# Battery_Management.net
KiCad netlist of a schematic drawn in Altium Designer
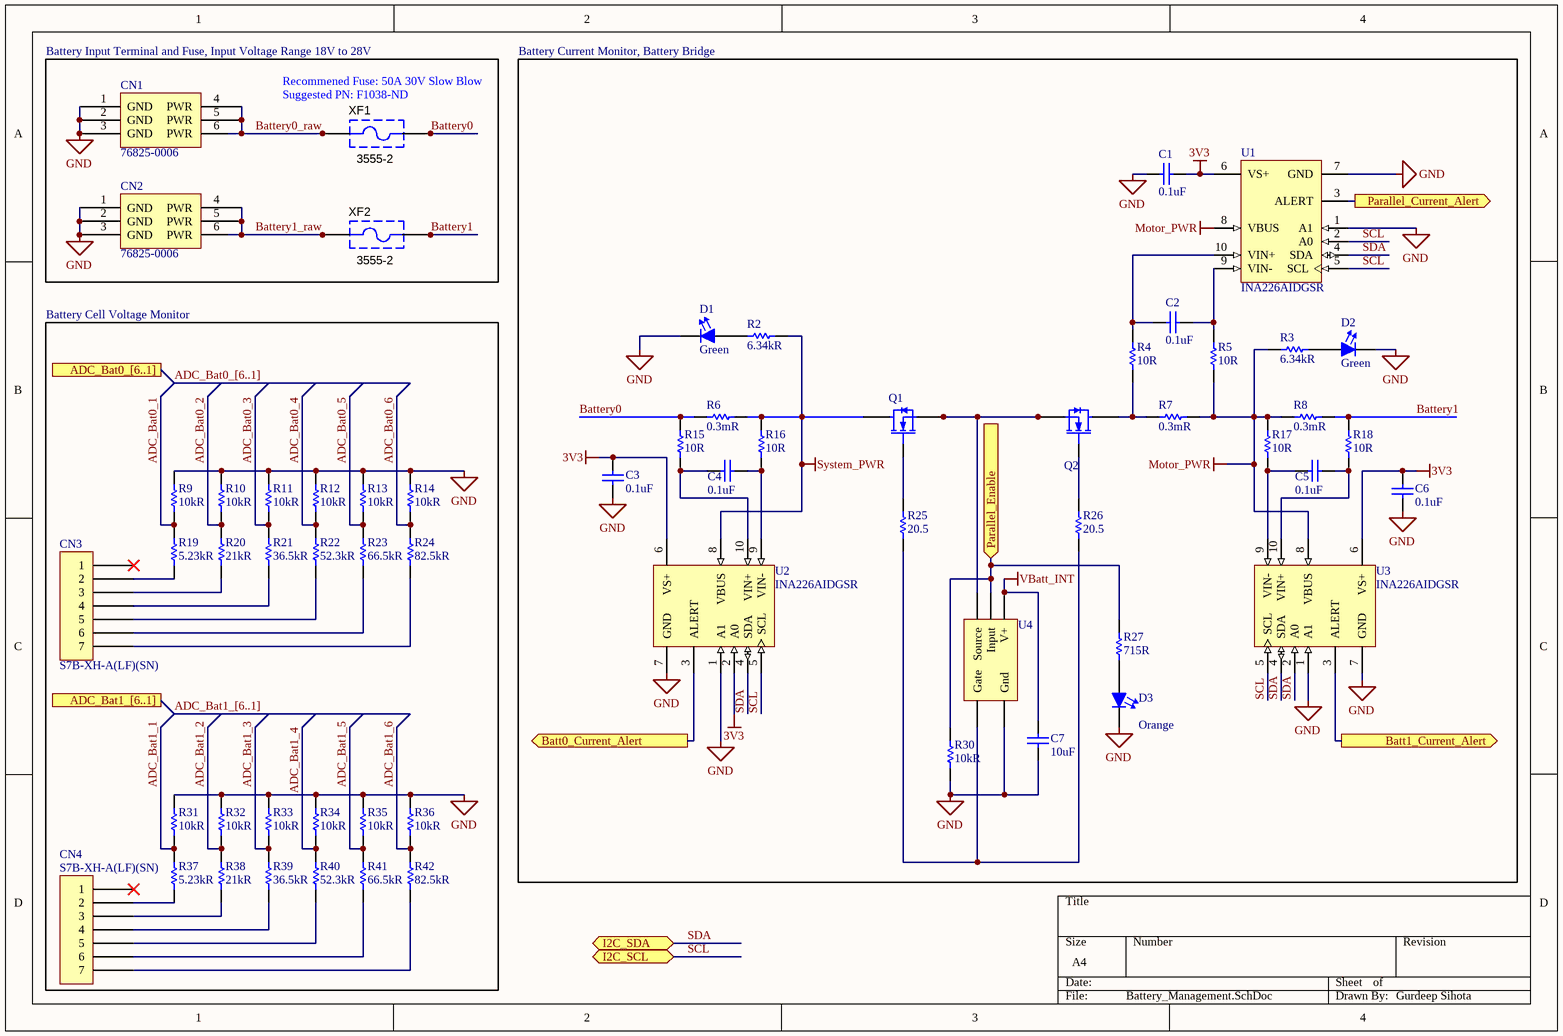
[diagram p0: Battery_Management.SchDoc]

(export (version "E")
  (design (tool "Eeschema 10.0.6"))
  (components
    (comp (ref "C1")
      (value "CL10B104JB8NNNC")
      (footprint "FP-CL10-0_1-IPC_A")
      (description "CAP CER 0.1UF 50V X7R 0603")
      (fields
        (field (name "TOLERANCE") "5%")
        (field (name "VOLTAGE") "50V")
        (field (name "CAPACITANCE") "0.1uF")
      )
      (libsource (lib "AUVIC") (part "CAP-NP-2"))
    )
    (comp (ref "C2")
      (value "CL10B104JB8NNNC")
      (footprint "FP-CL10-0_1-IPC_A")
      (description "CAP CER 0.1UF 50V X7R 0603")
      (fields
        (field (name "TOLERANCE") "5%")
        (field (name "VOLTAGE") "50V")
        (field (name "CAPACITANCE") "0.1uF")
      )
      (libsource (lib "AUVIC") (part "CAP-NP-2"))
    )
    (comp (ref "C3")
      (value "CL10B104JB8NNNC")
      (footprint "FP-CL10-0_1-IPC_A")
      (description "CAP CER 0.1UF 50V X7R 0603")
      (fields
        (field (name "TOLERANCE") "5%")
        (field (name "VOLTAGE") "50V")
        (field (name "CAPACITANCE") "0.1uF")
      )
      (libsource (lib "AUVIC") (part "CAP-NP-2"))
    )
    (comp (ref "C4")
      (value "CL10B104JB8NNNC")
      (footprint "FP-CL10-0_1-IPC_A")
      (description "CAP CER 0.1UF 50V X7R 0603")
      (fields
        (field (name "TOLERANCE") "5%")
        (field (name "VOLTAGE") "50V")
        (field (name "CAPACITANCE") "0.1uF")
      )
      (libsource (lib "AUVIC") (part "CAP-NP-2"))
    )
    (comp (ref "C5")
      (value "CL10B104JB8NNNC")
      (footprint "FP-CL10-0_1-IPC_A")
      (description "CAP CER 0.1UF 50V X7R 0603")
      (fields
        (field (name "TOLERANCE") "5%")
        (field (name "VOLTAGE") "50V")
        (field (name "CAPACITANCE") "0.1uF")
      )
      (libsource (lib "AUVIC") (part "CAP-NP-2"))
    )
    (comp (ref "C6")
      (value "CL10B104JB8NNNC")
      (footprint "FP-CL10-0_1-IPC_A")
      (description "CAP CER 0.1UF 50V X7R 0603")
      (fields
        (field (name "TOLERANCE") "5%")
        (field (name "VOLTAGE") "50V")
        (field (name "CAPACITANCE") "0.1uF")
      )
      (libsource (lib "AUVIC") (part "CAP-NP-2"))
    )
    (comp (ref "C7")
      (value "CL31B106KBHNNNE")
      (footprint "CAPC3216X180X50ML20T30")
      (description "Cap Ceramic 10uF 50V X7R 10% Pad SMD 1206 125°C T/R")
      (fields (field (name "CAPACITANCE") "10uF") (field (name "TOLERANCE") "10%"))
      (libsource (lib "AUVIC") (part "CAP-NP-2"))
    )
    (comp (ref "CN1")
      (value "76825-0006")
      (footprint "76825-0006-Footprint-1")
      (libsource (lib "AUVIC") (part "76825-0006"))
    )
    (comp (ref "CN2")
      (value "76825-0006")
      (footprint "76825-0006-Footprint-1")
      (libsource (lib "AUVIC") (part "76825-0006"))
    )
    (comp (ref "CN3")
      (value "S7B-XH-A(LF)(SN)")
      (footprint "S7B-XH-A(LF)(SN)-Footprint-1")
      (description "CONN HEADER XH SIDE 7POS 2.5MM")
      (libsource (lib "AUVIC") (part "S7B-XH-A(LF)(SN)"))
    )
    (comp (ref "CN4")
      (value "S7B-XH-A(LF)(SN)")
      (footprint "S7B-XH-A(LF)(SN)-Footprint-1")
      (description "CONN HEADER XH SIDE 7POS 2.5MM")
      (libsource (lib "AUVIC") (part "S7B-XH-A(LF)(SN)"))
    )
    (comp (ref "D1")
      (value "LT Q39G-Q1OO-25-1")
      (footprint "FP-LB_Q39E-MFG")
      (description "LED GREEN DIFFUSED 0603 SMD")
      (fields (field (name "COLOR") "Green"))
      (libsource (lib "") (part "Symbol_1"))
    )
    (comp (ref "D2")
      (value "LT Q39G-Q1OO-25-1")
      (footprint "FP-LB_Q39E-MFG")
      (description "LED GREEN DIFFUSED 0603 SMD")
      (fields (field (name "COLOR") "Green"))
      (libsource (lib "") (part "Symbol_1"))
    )
    (comp (ref "D3")
      (value "LED, 0805 (2012), Orange, Clear")
      (footprint "LED0805")
      (fields (field (name "COLOUR") "Orange") (field (name "CREATED BY") "Robert Keen"))
      (libsource (lib "") (part "Symbol_1"))
    )
    (comp (ref "Q1")
      (value "MOSFET N-Channel, 40V, 100A, 272W")
      (footprint "LFPAK-PowerSO8")
      (description "MOSFET N-Channel, 40V, 100A, 272W, Enh-Mode")
      (fields
        (field (name "MFG") "NXP Semiconductors")
        (field (name "PUBLISHER") "AUVic")
        (field (name "CREATED BY") "Ashwin Sira")
        (field (name "REVIEWED_BY") "Ashwin Sira")
      )
      (libsource (lib "AUVIC") (part "MOSFET N-Channel, 40V, 100A, 272W"))
    )
    (comp (ref "Q2")
      (value "MOSFET N-Channel, 40V, 100A, 272W")
      (footprint "LFPAK-PowerSO8")
      (description "MOSFET N-Channel, 40V, 100A, 272W, Enh-Mode")
      (fields
        (field (name "MFG") "NXP Semiconductors")
        (field (name "PUBLISHER") "AUVic")
        (field (name "CREATED BY") "Ashwin Sira")
        (field (name "REVIEWED_BY") "Ashwin Sira")
      )
      (libsource (lib "AUVIC") (part "MOSFET N-Channel, 40V, 100A, 272W"))
    )
    (comp (ref "R2")
      (value "CRCW06036K34FKEA")
      (footprint "RESC1609X50X30ML10T20")
      (fields (field (name "RESISTANCE") "6.34kR") (field (name "TOLERANCE") "1%"))
      (libsource (lib "AUVIC") (part "RES"))
    )
    (comp (ref "R3")
      (value "CRCW06036K34FKEA")
      (footprint "RESC1609X50X30ML10T20")
      (fields (field (name "RESISTANCE") "6.34kR") (field (name "TOLERANCE") "1%"))
      (libsource (lib "AUVIC") (part "RES"))
    )
    (comp (ref "R4")
      (value "ERJ3EKF10R0V")
      (footprint "FP-ERJ3EK-IPC_A")
      (fields (field (name "RESISTANCE") "10R") (field (name "TOLERANCE") "1%"))
      (libsource (lib "AUVIC") (part "RES"))
    )
    (comp (ref "R5")
      (value "ERJ3EKF10R0V")
      (footprint "FP-ERJ3EK-IPC_A")
      (fields (field (name "RESISTANCE") "10R") (field (name "TOLERANCE") "1%"))
      (libsource (lib "AUVIC") (part "RES"))
    )
    (comp (ref "R6")
      (value "HCS2512FTL300")
      (footprint "RESC6332N(2512\")")
      (fields (field (name "RESISTANCE") "0.3mR") (field (name "TOLERANCE") "1%"))
      (libsource (lib "AUVIC") (part "Symbol"))
    )
    (comp (ref "R7")
      (value "HCS2512FTL300")
      (footprint "RESC6332N(2512\")")
      (fields (field (name "RESISTANCE") "0.3mR") (field (name "TOLERANCE") "1%"))
      (libsource (lib "AUVIC") (part "Symbol"))
    )
    (comp (ref "R8")
      (value "HCS2512FTL300")
      (footprint "RESC6332N(2512\")")
      (fields (field (name "RESISTANCE") "0.3mR") (field (name "TOLERANCE") "1%"))
      (libsource (lib "AUVIC") (part "Symbol"))
    )
    (comp (ref "R9")
      (value "RC0603FR-0710KL")
      (footprint "RESC1608X55X25ML10T15")
      (description "Res General Purpose Thick Film 0603 10K Ohm 1% 1/10W ±100ppm/°C Molded SMD Paper T/R")
      (fields (field (name "RESISTANCE") "10kR") (field (name "TOLERANCE") "1%"))
      (libsource (lib "AUVIC") (part "RES-2"))
    )
    (comp (ref "R10")
      (value "RC0603FR-0710KL")
      (footprint "RESC1608X55X25ML10T15")
      (description "Res General Purpose Thick Film 0603 10K Ohm 1% 1/10W ±100ppm/°C Molded SMD Paper T/R")
      (fields (field (name "RESISTANCE") "10kR") (field (name "TOLERANCE") "1%"))
      (libsource (lib "AUVIC") (part "RES-2"))
    )
    (comp (ref "R11")
      (value "RC0603FR-0710KL")
      (footprint "RESC1608X55X25ML10T15")
      (description "Res General Purpose Thick Film 0603 10K Ohm 1% 1/10W ±100ppm/°C Molded SMD Paper T/R")
      (fields (field (name "RESISTANCE") "10kR") (field (name "TOLERANCE") "1%"))
      (libsource (lib "AUVIC") (part "RES-2"))
    )
    (comp (ref "R12")
      (value "RC0603FR-0710KL")
      (footprint "RESC1608X55X25ML10T15")
      (description "Res General Purpose Thick Film 0603 10K Ohm 1% 1/10W ±100ppm/°C Molded SMD Paper T/R")
      (fields (field (name "RESISTANCE") "10kR") (field (name "TOLERANCE") "1%"))
      (libsource (lib "AUVIC") (part "RES-2"))
    )
    (comp (ref "R13")
      (value "RC0603FR-0710KL")
      (footprint "RESC1608X55X25ML10T15")
      (description "Res General Purpose Thick Film 0603 10K Ohm 1% 1/10W ±100ppm/°C Molded SMD Paper T/R")
      (fields (field (name "RESISTANCE") "10kR") (field (name "TOLERANCE") "1%"))
      (libsource (lib "AUVIC") (part "RES-2"))
    )
    (comp (ref "R14")
      (value "RC0603FR-0710KL")
      (footprint "RESC1608X55X25ML10T15")
      (description "Res General Purpose Thick Film 0603 10K Ohm 1% 1/10W ±100ppm/°C Molded SMD Paper T/R")
      (fields (field (name "RESISTANCE") "10kR") (field (name "TOLERANCE") "1%"))
      (libsource (lib "AUVIC") (part "RES-2"))
    )
    (comp (ref "R15")
      (value "ERJ3EKF10R0V")
      (footprint "FP-ERJ3EK-IPC_A")
      (fields (field (name "RESISTANCE") "10R") (field (name "TOLERANCE") "1%"))
      (libsource (lib "AUVIC") (part "RES"))
    )
    (comp (ref "R16")
      (value "ERJ3EKF10R0V")
      (footprint "FP-ERJ3EK-IPC_A")
      (fields (field (name "RESISTANCE") "10R") (field (name "TOLERANCE") "1%"))
      (libsource (lib "AUVIC") (part "RES"))
    )
    (comp (ref "R17")
      (value "ERJ3EKF10R0V")
      (footprint "FP-ERJ3EK-IPC_A")
      (fields (field (name "RESISTANCE") "10R") (field (name "TOLERANCE") "1%"))
      (libsource (lib "AUVIC") (part "RES"))
    )
    (comp (ref "R18")
      (value "ERJ3EKF10R0V")
      (footprint "FP-ERJ3EK-IPC_A")
      (fields (field (name "RESISTANCE") "10R") (field (name "TOLERANCE") "1%"))
      (libsource (lib "AUVIC") (part "RES"))
    )
    (comp (ref "R19")
      (value "ERJ-3EKF5231V")
      (footprint "RESC1608X55X30ML15T15")
      (description "GLOVE, POLYAMIDE, L/FREE, PU, SIZE 6 - More Details")
      (fields (field (name "RESISTANCE") "5.23kR") (field (name "TOLERANCE") "1%"))
      (libsource (lib "AUVIC") (part "RES"))
    )
    (comp (ref "R20")
      (value "ERJ-3EKF2102V")
      (footprint "RESC1608X55X30ML15T15")
      (description "RESISTOR, 0603, 21K 1%, 0.1W")
      (fields (field (name "RESISTANCE") "21kR") (field (name "TOLERANCE") "1%"))
      (libsource (lib "AUVIC") (part "RES"))
    )
    (comp (ref "R21")
      (value "ERJ3EKF3652V")
      (footprint "RESC1608X55X30ML15T15")
      (fields (field (name "RESISTANCE") "36.5kR") (field (name "TOLERANCE") "1%"))
      (libsource (lib "AUVIC") (part "RES"))
    )
    (comp (ref "R22")
      (value "ERJ-3EKF5232V")
      (footprint "RESC1608X55X30ML15T15")
      (fields (field (name "RESISTANCE") "52.3kR") (field (name "TOLERANCE") "1%"))
      (libsource (lib "AUVIC") (part "RES"))
    )
    (comp (ref "R23")
      (value "ERJ-3EKF6652V")
      (footprint "RESC1608X55X30ML15T15")
      (fields (field (name "RESISTANCE") "66.5kR") (field (name "TOLERANCE") "1%"))
      (libsource (lib "AUVIC") (part "RES"))
    )
    (comp (ref "R24")
      (value "ERJ-3EKF8252V")
      (footprint "RESC1608X55X30ML15T15")
      (description "RES SMD 82.5K OHM 1% 1/10W 0603")
      (fields (field (name "RESISTANCE") "82.5kR") (field (name "TOLERANCE") "1%"))
      (libsource (lib "AUVIC") (part "RES"))
    )
    (comp (ref "R25")
      (value "20.5")
      (footprint "RESC1608N(0603\")")
      (description "20.5 Ohm, 1%, 1/10W , 0603, SMD")
      (fields (field (name "PUBLISHER") "AUVic") (field (name "CREATED BY") "Gabriel Green"))
      (libsource (lib "AUVIC") (part "Symbol"))
    )
    (comp (ref "R26")
      (value "20.5")
      (footprint "RESC1608N(0603\")")
      (description "20.5 Ohm, 1%, 1/10W , 0603, SMD")
      (fields (field (name "PUBLISHER") "AUVic") (field (name "CREATED BY") "Gabriel Green"))
      (libsource (lib "AUVIC") (part "Symbol"))
    )
    (comp (ref "R27")
      (value "715R")
      (footprint "RESC1608N(0603\")")
      (description "715R, 1%, 1/10W, 0603, SMD")
      (fields (field (name "PUBLISHER") "AUVic") (field (name "CREATED BY") "Ashwin Sira"))
      (libsource (lib "AUVIC") (part "Symbol"))
    )
    (comp (ref "R30")
      (value "RC0603FR-0710KL")
      (footprint "RESC1608X55X25ML10T15")
      (description "Res General Purpose Thick Film 0603 10K Ohm 1% 1/10W ±100ppm/°C Molded SMD Paper T/R")
      (fields (field (name "RESISTANCE") "10kR") (field (name "TOLERANCE") "1%"))
      (libsource (lib "AUVIC") (part "RES-2"))
    )
    (comp (ref "R31")
      (value "RC0603FR-0710KL")
      (footprint "RESC1608X55X25ML10T15")
      (description "Res General Purpose Thick Film 0603 10K Ohm 1% 1/10W ±100ppm/°C Molded SMD Paper T/R")
      (fields (field (name "RESISTANCE") "10kR") (field (name "TOLERANCE") "1%"))
      (libsource (lib "AUVIC") (part "RES-2"))
    )
    (comp (ref "R32")
      (value "RC0603FR-0710KL")
      (footprint "RESC1608X55X25ML10T15")
      (description "Res General Purpose Thick Film 0603 10K Ohm 1% 1/10W ±100ppm/°C Molded SMD Paper T/R")
      (fields (field (name "RESISTANCE") "10kR") (field (name "TOLERANCE") "1%"))
      (libsource (lib "AUVIC") (part "RES-2"))
    )
    (comp (ref "R33")
      (value "RC0603FR-0710KL")
      (footprint "RESC1608X55X25ML10T15")
      (description "Res General Purpose Thick Film 0603 10K Ohm 1% 1/10W ±100ppm/°C Molded SMD Paper T/R")
      (fields (field (name "RESISTANCE") "10kR") (field (name "TOLERANCE") "1%"))
      (libsource (lib "AUVIC") (part "RES-2"))
    )
    (comp (ref "R34")
      (value "RC0603FR-0710KL")
      (footprint "RESC1608X55X25ML10T15")
      (description "Res General Purpose Thick Film 0603 10K Ohm 1% 1/10W ±100ppm/°C Molded SMD Paper T/R")
      (fields (field (name "RESISTANCE") "10kR") (field (name "TOLERANCE") "1%"))
      (libsource (lib "AUVIC") (part "RES-2"))
    )
    (comp (ref "R35")
      (value "RC0603FR-0710KL")
      (footprint "RESC1608X55X25ML10T15")
      (description "Res General Purpose Thick Film 0603 10K Ohm 1% 1/10W ±100ppm/°C Molded SMD Paper T/R")
      (fields (field (name "RESISTANCE") "10kR") (field (name "TOLERANCE") "1%"))
      (libsource (lib "AUVIC") (part "RES-2"))
    )
    (comp (ref "R36")
      (value "RC0603FR-0710KL")
      (footprint "RESC1608X55X25ML10T15")
      (description "Res General Purpose Thick Film 0603 10K Ohm 1% 1/10W ±100ppm/°C Molded SMD Paper T/R")
      (fields (field (name "RESISTANCE") "10kR") (field (name "TOLERANCE") "1%"))
      (libsource (lib "AUVIC") (part "RES-2"))
    )
    (comp (ref "R37")
      (value "ERJ-3EKF5231V")
      (footprint "RESC1608X55X30ML15T15")
      (description "GLOVE, POLYAMIDE, L/FREE, PU, SIZE 6 - More Details")
      (fields (field (name "RESISTANCE") "5.23kR") (field (name "TOLERANCE") "1%"))
      (libsource (lib "AUVIC") (part "RES"))
    )
    (comp (ref "R38")
      (value "ERJ-3EKF2102V")
      (footprint "RESC1608X55X30ML15T15")
      (description "RESISTOR, 0603, 21K 1%, 0.1W")
      (fields (field (name "RESISTANCE") "21kR") (field (name "TOLERANCE") "1%"))
      (libsource (lib "AUVIC") (part "RES"))
    )
    (comp (ref "R39")
      (value "ERJ3EKF3652V")
      (footprint "RESC1608X55X30ML15T15")
      (fields (field (name "RESISTANCE") "36.5kR") (field (name "TOLERANCE") "1%"))
      (libsource (lib "AUVIC") (part "RES"))
    )
    (comp (ref "R40")
      (value "ERJ-3EKF5232V")
      (footprint "RESC1608X55X30ML15T15")
      (fields (field (name "RESISTANCE") "52.3kR") (field (name "TOLERANCE") "1%"))
      (libsource (lib "AUVIC") (part "RES"))
    )
    (comp (ref "R41")
      (value "ERJ-3EKF6652V")
      (footprint "RESC1608X55X30ML15T15")
      (fields (field (name "RESISTANCE") "66.5kR") (field (name "TOLERANCE") "1%"))
      (libsource (lib "AUVIC") (part "RES"))
    )
    (comp (ref "R42")
      (value "ERJ-3EKF8252V")
      (footprint "RESC1608X55X30ML15T15")
      (description "RES SMD 82.5K OHM 1% 1/10W 0603")
      (fields (field (name "RESISTANCE") "82.5kR") (field (name "TOLERANCE") "1%"))
      (libsource (lib "AUVIC") (part "RES"))
    )
    (comp (ref "U1")
      (value "INA226AIDGSR")
      (footprint "DGS0010A_M")
      (description "Bi Directional Current and Power Monitor 10-Pin VSSOP T/R")
      (libsource (lib "AUVIC") (part "TI-INA226DGS10"))
    )
    (comp (ref "U2")
      (value "INA226AIDGSR")
      (footprint "DGS0010A_M")
      (description "Bi Directional Current and Power Monitor 10-Pin VSSOP T/R")
      (libsource (lib "") (part "TI-INA226DGS10_2"))
    )
    (comp (ref "U3")
      (value "INA226AIDGSR")
      (footprint "DGS0010A_M")
      (description "Bi Directional Current and Power Monitor 10-Pin VSSOP T/R")
      (libsource (lib "") (part "TI-INA226DGS10_1"))
    )
    (comp (ref "U4")
      (value "MIC5014YM-TR")
      (footprint "SOC 8")
      (description "High-Side or Low-Side Gate Driver IC Non-Inverting 8-SOIC")
      (libsource (lib "AUVIC") (part "Gate Driver TTL Logic 3 - 30V"))
    )
    (comp (ref "XF1")
      (value "3555-2")
      (footprint "3555-2-Footprint-1")
      (description "FUSE HOLDER MAXI AUTO BLADE PC")
      (fields (field (name "VOLTAGE") "500V"))
      (libsource (lib "AUVIC") (part "FUSE_HOLDER-4"))
    )
    (comp (ref "XF2")
      (value "3555-2")
      (footprint "3555-2-Footprint-1")
      (description "FUSE HOLDER MAXI AUTO BLADE PC")
      (fields (field (name "VOLTAGE") "500V"))
      (libsource (lib "AUVIC") (part "FUSE_HOLDER-4"))
    )
  )
  (nets
    (net (code "1") (name "/ADC_Bat0_1") (class "Default")
      (node (ref "R19") (pin "2") (pinfunction "2_2") (pintype "passive"))
      (node (ref "R9") (pin "1") (pinfunction "1_1") (pintype "passive"))
    )
    (net (code "2") (name "/ADC_Bat0_2") (class "Default")
      (node (ref "R10") (pin "2") (pinfunction "2_2") (pintype "passive"))
      (node (ref "R20") (pin "2") (pinfunction "2_2") (pintype "passive"))
    )
    (net (code "3") (name "/ADC_Bat0_3") (class "Default")
      (node (ref "R11") (pin "1") (pinfunction "1_1") (pintype "passive"))
      (node (ref "R21") (pin "2") (pinfunction "2_2") (pintype "passive"))
    )
    (net (code "4") (name "/ADC_Bat0_4") (class "Default")
      (node (ref "R12") (pin "1") (pinfunction "1_1") (pintype "passive"))
      (node (ref "R22") (pin "1") (pinfunction "1_1") (pintype "passive"))
    )
    (net (code "5") (name "/ADC_Bat0_5") (class "Default")
      (node (ref "R13") (pin "1") (pinfunction "1_1") (pintype "passive"))
      (node (ref "R23") (pin "2") (pinfunction "2_2") (pintype "passive"))
    )
    (net (code "6") (name "/ADC_Bat0_6") (class "Default")
      (node (ref "R14") (pin "1") (pinfunction "1_1") (pintype "passive"))
      (node (ref "R24") (pin "2") (pinfunction "2_2") (pintype "passive"))
    )
    (net (code "8") (name "/ADC_Bat1_1") (class "Default")
      (node (ref "R31") (pin "2") (pinfunction "2_2") (pintype "passive"))
      (node (ref "R37") (pin "2") (pinfunction "2_2") (pintype "passive"))
    )
    (net (code "9") (name "/ADC_Bat1_2") (class "Default")
      (node (ref "R32") (pin "2") (pinfunction "2_2") (pintype "passive"))
      (node (ref "R38") (pin "2") (pinfunction "2_2") (pintype "passive"))
    )
    (net (code "10") (name "/ADC_Bat1_3") (class "Default")
      (node (ref "R33") (pin "1") (pinfunction "1_1") (pintype "passive"))
      (node (ref "R39") (pin "2") (pinfunction "2_2") (pintype "passive"))
    )
    (net (code "11") (name "/ADC_Bat1_4") (class "Default")
      (node (ref "R34") (pin "1") (pinfunction "1_1") (pintype "passive"))
      (node (ref "R40") (pin "1") (pinfunction "1_1") (pintype "passive"))
    )
    (net (code "12") (name "/ADC_Bat1_5") (class "Default")
      (node (ref "R35") (pin "1") (pinfunction "1_1") (pintype "passive"))
      (node (ref "R41") (pin "2") (pinfunction "2_2") (pintype "passive"))
    )
    (net (code "13") (name "/ADC_Bat1_6") (class "Default")
      (node (ref "R36") (pin "1") (pinfunction "1_1") (pintype "passive"))
      (node (ref "R42") (pin "2") (pinfunction "2_2") (pintype "passive"))
    )
    (net (code "15") (name "/Batt0_Current_Alert") (class "Default")
      (node (ref "U2") (pin "3") (pinfunction "ALERT_3") (pintype "open_collector"))
    )
    (net (code "16") (name "/Batt1_Current_Alert") (class "Default")
      (node (ref "U3") (pin "3") (pinfunction "ALERT_3") (pintype "open_collector"))
    )
    (net (code "17") (name "/Battery0") (class "Default")
      (node (ref "R15") (pin "1") (pinfunction "1_1") (pintype "passive"))
      (node (ref "R6") (pin "1") (pinfunction "1_1") (pintype "passive"))
      (node (ref "XF1") (pin "3") (pinfunction "3_3") (pintype "passive"))
      (node (ref "XF1") (pin "4") (pinfunction "4_4") (pintype "passive"))
    )
    (net (code "18") (name "/Battery0_raw") (class "Default")
      (node (ref "CN1") (pin "4") (pinfunction "PWR_4") (pintype "passive"))
      (node (ref "CN1") (pin "5") (pinfunction "PWR_5") (pintype "passive"))
      (node (ref "CN1") (pin "6") (pinfunction "PWR_6") (pintype "passive"))
      (node (ref "XF1") (pin "1") (pinfunction "1_1") (pintype "passive"))
      (node (ref "XF1") (pin "2") (pinfunction "2_2") (pintype "passive"))
    )
    (net (code "19") (name "/Battery1") (class "Default")
      (node (ref "R18") (pin "1") (pinfunction "1_1") (pintype "passive"))
      (node (ref "R8") (pin "2") (pinfunction "2_2") (pintype "passive"))
      (node (ref "XF2") (pin "3") (pinfunction "3_3") (pintype "passive"))
      (node (ref "XF2") (pin "4") (pinfunction "4_4") (pintype "passive"))
    )
    (net (code "20") (name "/Battery1_raw") (class "Default")
      (node (ref "CN2") (pin "4") (pinfunction "PWR_4") (pintype "passive"))
      (node (ref "CN2") (pin "5") (pinfunction "PWR_5") (pintype "passive"))
      (node (ref "CN2") (pin "6") (pinfunction "PWR_6") (pintype "passive"))
      (node (ref "XF2") (pin "1") (pinfunction "1_1") (pintype "passive"))
      (node (ref "XF2") (pin "2") (pinfunction "2_2") (pintype "passive"))
    )
    (net (code "21") (name "/Parallel_Current_Alert") (class "Default")
      (node (ref "U1") (pin "3") (pinfunction "ALERT_3") (pintype "open_collector"))
    )
    (net (code "22") (name "/Parallel_Enable") (class "Default")
      (node (ref "R27") (pin "1") (pinfunction "1_1") (pintype "passive"))
      (node (ref "R30") (pin "2") (pinfunction "2_2") (pintype "passive"))
      (node (ref "U4") (pin "2") (pinfunction "Input_2") (pintype "passive"))
    )
    (net (code "23") (name "/SCL") (class "Default")
      (node (ref "U1") (pin "2") (pinfunction "A0_2") (pintype "input"))
      (node (ref "U1") (pin "5") (pinfunction "SCL_5") (pintype "input"))
      (node (ref "U2") (pin "5") (pinfunction "SCL_5") (pintype "input"))
      (node (ref "U3") (pin "5") (pinfunction "SCL_5") (pintype "input"))
    )
    (net (code "24") (name "/SDA") (class "Default")
      (node (ref "U1") (pin "4") (pinfunction "SDA_4") (pintype "bidirectional"))
      (node (ref "U2") (pin "4") (pinfunction "SDA_4") (pintype "bidirectional"))
      (node (ref "U3") (pin "2") (pinfunction "A0_2") (pintype "input"))
      (node (ref "U3") (pin "4") (pinfunction "SDA_4") (pintype "bidirectional"))
    )
    (net (code "25") (name "3V3") (class "Default")
      (node (ref "C1") (pin "1") (pinfunction "1_1") (pintype "passive"))
      (node (ref "C3") (pin "1") (pinfunction "1_1") (pintype "passive"))
      (node (ref "C6") (pin "1") (pinfunction "1_1") (pintype "passive"))
      (node (ref "U1") (pin "6") (pinfunction "VS+_6") (pintype "power_in"))
      (node (ref "U2") (pin "2") (pinfunction "A0_2") (pintype "input"))
      (node (ref "U2") (pin "6") (pinfunction "VS+_6") (pintype "power_in"))
      (node (ref "U3") (pin "6") (pinfunction "VS+_6") (pintype "power_in"))
    )
    (net (code "26") (name "GND") (class "Default")
      (node (ref "C1") (pin "2") (pinfunction "2_2") (pintype "passive"))
      (node (ref "C3") (pin "2") (pinfunction "2_2") (pintype "passive"))
      (node (ref "C6") (pin "2") (pinfunction "2_2") (pintype "passive"))
      (node (ref "C7") (pin "2") (pinfunction "2_2") (pintype "passive"))
      (node (ref "CN1") (pin "1") (pinfunction "GND_1") (pintype "passive"))
      (node (ref "CN1") (pin "2") (pinfunction "GND_2") (pintype "passive"))
      (node (ref "CN1") (pin "3") (pinfunction "GND_3") (pintype "passive"))
      (node (ref "CN2") (pin "1") (pinfunction "GND_1") (pintype "passive"))
      (node (ref "CN2") (pin "2") (pinfunction "GND_2") (pintype "passive"))
      (node (ref "CN2") (pin "3") (pinfunction "GND_3") (pintype "passive"))
      (node (ref "D1") (pin "1") (pinfunction "Cathode_1") (pintype "passive"))
      (node (ref "D2") (pin "1") (pinfunction "Cathode_1") (pintype "passive"))
      (node (ref "D3") (pin "1") (pinfunction "Cathode_1") (pintype "passive"))
      (node (ref "R10") (pin "1") (pinfunction "1_1") (pintype "passive"))
      (node (ref "R11") (pin "2") (pinfunction "2_2") (pintype "passive"))
      (node (ref "R12") (pin "2") (pinfunction "2_2") (pintype "passive"))
      (node (ref "R13") (pin "2") (pinfunction "2_2") (pintype "passive"))
      (node (ref "R14") (pin "2") (pinfunction "2_2") (pintype "passive"))
      (node (ref "R30") (pin "1") (pinfunction "1_1") (pintype "passive"))
      (node (ref "R31") (pin "1") (pinfunction "1_1") (pintype "passive"))
      (node (ref "R32") (pin "1") (pinfunction "1_1") (pintype "passive"))
      (node (ref "R33") (pin "2") (pinfunction "2_2") (pintype "passive"))
      (node (ref "R34") (pin "2") (pinfunction "2_2") (pintype "passive"))
      (node (ref "R35") (pin "2") (pinfunction "2_2") (pintype "passive"))
      (node (ref "R36") (pin "2") (pinfunction "2_2") (pintype "passive"))
      (node (ref "R9") (pin "2") (pinfunction "2_2") (pintype "passive"))
      (node (ref "U1") (pin "1") (pinfunction "A1_1") (pintype "input"))
      (node (ref "U1") (pin "7") (pinfunction "GND_7") (pintype "power_in"))
      (node (ref "U2") (pin "1") (pinfunction "A1_1") (pintype "input"))
      (node (ref "U2") (pin "7") (pinfunction "GND_7") (pintype "power_in"))
      (node (ref "U3") (pin "1") (pinfunction "A1_1") (pintype "input"))
      (node (ref "U3") (pin "7") (pinfunction "GND_7") (pintype "power_in"))
      (node (ref "U4") (pin "4") (pinfunction "Gnd_4") (pintype "passive"))
    )
    (net (code "27") (name "Motor_PWR") (class "Default")
      (node (ref "R17") (pin "1") (pinfunction "1_1") (pintype "passive"))
      (node (ref "R3") (pin "1") (pinfunction "1_1") (pintype "passive"))
      (node (ref "R5") (pin "1") (pinfunction "1_1") (pintype "passive"))
      (node (ref "R7") (pin "2") (pinfunction "2_2") (pintype "passive"))
      (node (ref "R8") (pin "1") (pinfunction "1_1") (pintype "passive"))
      (node (ref "U1") (pin "8") (pinfunction "VBUS_8") (pintype "input"))
      (node (ref "U3") (pin "8") (pinfunction "VBUS_8") (pintype "input"))
    )
    (net (code "28") (name "Net-(CN3-Pad2)") (class "Default")
      (node (ref "CN3") (pin "2") (pinfunction "2_2") (pintype "passive"))
      (node (ref "R19") (pin "1") (pinfunction "1_1") (pintype "passive"))
    )
    (net (code "29") (name "Net-(CN3-Pad3)") (class "Default")
      (node (ref "CN3") (pin "3") (pinfunction "3_3") (pintype "passive"))
      (node (ref "R20") (pin "1") (pinfunction "1_1") (pintype "passive"))
    )
    (net (code "30") (name "Net-(CN3-Pad4)") (class "Default")
      (node (ref "CN3") (pin "4") (pinfunction "4_4") (pintype "passive"))
      (node (ref "R21") (pin "1") (pinfunction "1_1") (pintype "passive"))
    )
    (net (code "31") (name "Net-(CN3-Pad5)") (class "Default")
      (node (ref "CN3") (pin "5") (pinfunction "5_5") (pintype "passive"))
      (node (ref "R22") (pin "2") (pinfunction "2_2") (pintype "passive"))
    )
    (net (code "32") (name "Net-(CN3-Pad6)") (class "Default")
      (node (ref "CN3") (pin "6") (pinfunction "6_6") (pintype "passive"))
      (node (ref "R23") (pin "1") (pinfunction "1_1") (pintype "passive"))
    )
    (net (code "33") (name "Net-(CN3-Pad7)") (class "Default")
      (node (ref "CN3") (pin "7") (pinfunction "7_7") (pintype "passive"))
      (node (ref "R24") (pin "1") (pinfunction "1_1") (pintype "passive"))
    )
    (net (code "34") (name "Net-(CN4-Pad2)") (class "Default")
      (node (ref "CN4") (pin "2") (pinfunction "2_2") (pintype "passive"))
      (node (ref "R37") (pin "1") (pinfunction "1_1") (pintype "passive"))
    )
    (net (code "35") (name "Net-(CN4-Pad3)") (class "Default")
      (node (ref "CN4") (pin "3") (pinfunction "3_3") (pintype "passive"))
      (node (ref "R38") (pin "1") (pinfunction "1_1") (pintype "passive"))
    )
    (net (code "36") (name "Net-(CN4-Pad4)") (class "Default")
      (node (ref "CN4") (pin "4") (pinfunction "4_4") (pintype "passive"))
      (node (ref "R39") (pin "1") (pinfunction "1_1") (pintype "passive"))
    )
    (net (code "37") (name "Net-(CN4-Pad5)") (class "Default")
      (node (ref "CN4") (pin "5") (pinfunction "5_5") (pintype "passive"))
      (node (ref "R40") (pin "2") (pinfunction "2_2") (pintype "passive"))
    )
    (net (code "38") (name "Net-(CN4-Pad6)") (class "Default")
      (node (ref "CN4") (pin "6") (pinfunction "6_6") (pintype "passive"))
      (node (ref "R41") (pin "1") (pinfunction "1_1") (pintype "passive"))
    )
    (net (code "39") (name "Net-(CN4-Pad7)") (class "Default")
      (node (ref "CN4") (pin "7") (pinfunction "7_7") (pintype "passive"))
      (node (ref "R42") (pin "1") (pinfunction "1_1") (pintype "passive"))
    )
    (net (code "40") (name "Net-(D1-Anode)") (class "Default")
      (node (ref "D1") (pin "2") (pinfunction "Anode_2") (pintype "passive"))
      (node (ref "R2") (pin "1") (pinfunction "1_1") (pintype "passive"))
    )
    (net (code "41") (name "Net-(D2-Anode)") (class "Default")
      (node (ref "D2") (pin "2") (pinfunction "Anode_2") (pintype "passive"))
      (node (ref "R3") (pin "2") (pinfunction "2_2") (pintype "passive"))
    )
    (net (code "42") (name "Net-(D3-Anode)") (class "Default")
      (node (ref "D3") (pin "2") (pinfunction "Anode_2") (pintype "passive"))
      (node (ref "R27") (pin "2") (pinfunction "2_2") (pintype "passive"))
    )
    (net (code "43") (name "Net-(Q1-Gate)") (class "Default")
      (node (ref "Q1") (pin "4") (pinfunction "Gate_4") (pintype "power_in"))
      (node (ref "R25") (pin "2") (pinfunction "2_2") (pintype "passive"))
    )
    (net (code "44") (name "Net-(Q2-Drain)") (class "Default")
      (node (ref "Q2") (pin "5") (pinfunction "Drain_5") (pintype "power_in"))
      (node (ref "R4") (pin "1") (pinfunction "1_1") (pintype "passive"))
      (node (ref "R7") (pin "1") (pinfunction "1_1") (pintype "passive"))
    )
    (net (code "45") (name "Net-(Q2-Gate)") (class "Default")
      (node (ref "Q2") (pin "4") (pinfunction "Gate_4") (pintype "power_in"))
      (node (ref "R26") (pin "2") (pinfunction "2_2") (pintype "passive"))
    )
    (net (code "46") (name "Net-(U1-VIN+)") (class "Default")
      (node (ref "C2") (pin "1") (pinfunction "1_1") (pintype "passive"))
      (node (ref "R4") (pin "2") (pinfunction "2_2") (pintype "passive"))
      (node (ref "U1") (pin "10") (pinfunction "VIN+_10") (pintype "input"))
    )
    (net (code "47") (name "Net-(U1-VIN-)") (class "Default")
      (node (ref "C2") (pin "2") (pinfunction "2_2") (pintype "passive"))
      (node (ref "R5") (pin "2") (pinfunction "2_2") (pintype "passive"))
      (node (ref "U1") (pin "9") (pinfunction "VIN-_9") (pintype "input"))
    )
    (net (code "48") (name "Net-(U2-VIN+)") (class "Default")
      (node (ref "C4") (pin "2") (pinfunction "2_2") (pintype "passive"))
      (node (ref "R15") (pin "2") (pinfunction "2_2") (pintype "passive"))
      (node (ref "U2") (pin "10") (pinfunction "VIN+_10") (pintype "input"))
    )
    (net (code "49") (name "Net-(U2-VIN-)") (class "Default")
      (node (ref "C4") (pin "1") (pinfunction "1_1") (pintype "passive"))
      (node (ref "R16") (pin "2") (pinfunction "2_2") (pintype "passive"))
      (node (ref "U2") (pin "9") (pinfunction "VIN-_9") (pintype "input"))
    )
    (net (code "50") (name "Net-(U3-VIN+)") (class "Default")
      (node (ref "C5") (pin "1") (pinfunction "1_1") (pintype "passive"))
      (node (ref "R18") (pin "2") (pinfunction "2_2") (pintype "passive"))
      (node (ref "U3") (pin "10") (pinfunction "VIN+_10") (pintype "input"))
    )
    (net (code "51") (name "Net-(U3-VIN-)") (class "Default")
      (node (ref "C5") (pin "2") (pinfunction "2_2") (pintype "passive"))
      (node (ref "R17") (pin "2") (pinfunction "2_2") (pintype "passive"))
      (node (ref "U3") (pin "9") (pinfunction "VIN-_9") (pintype "input"))
    )
    (net (code "52") (name "Net-(U4-Gate)") (class "Default")
      (node (ref "R25") (pin "1") (pinfunction "1_1") (pintype "passive"))
      (node (ref "R26") (pin "1") (pinfunction "1_1") (pintype "passive"))
      (node (ref "U4") (pin "5") (pinfunction "Gate_5") (pintype "passive"))
    )
    (net (code "53") (name "Net-(U4-Source)") (class "Default")
      (node (ref "Q1") (pin "1") (pinfunction "Source_1") (pintype "power_in"))
      (node (ref "Q1") (pin "2") (pinfunction "Source_2") (pintype "power_in"))
      (node (ref "Q1") (pin "3") (pinfunction "Source_3") (pintype "power_in"))
      (node (ref "Q2") (pin "1") (pinfunction "Source_1") (pintype "power_in"))
      (node (ref "Q2") (pin "2") (pinfunction "Source_2") (pintype "power_in"))
      (node (ref "Q2") (pin "3") (pinfunction "Source_3") (pintype "power_in"))
      (node (ref "U4") (pin "3") (pinfunction "Source_3") (pintype "passive"))
    )
    (net (code "54") (name "System_PWR") (class "Default")
      (node (ref "Q1") (pin "5") (pinfunction "Drain_5") (pintype "power_in"))
      (node (ref "R16") (pin "1") (pinfunction "1_1") (pintype "passive"))
      (node (ref "R2") (pin "2") (pinfunction "2_2") (pintype "passive"))
      (node (ref "R6") (pin "2") (pinfunction "2_2") (pintype "passive"))
      (node (ref "U2") (pin "8") (pinfunction "VBUS_8") (pintype "input"))
    )
    (net (code "55") (name "VBatt_INT") (class "Default")
      (node (ref "C7") (pin "1") (pinfunction "1_1") (pintype "passive"))
      (node (ref "U4") (pin "1") (pinfunction "V+_1") (pintype "passive"))
    )
    (net (code "56") (name "unconnected-(CN3-Pad1)") (class "Default")
      (node (ref "CN3") (pin "1") (pinfunction "1_1") (pintype "passive+no_connect"))
    )
    (net (code "57") (name "unconnected-(CN4-Pad1)") (class "Default")
      (node (ref "CN4") (pin "1") (pinfunction "1_1") (pintype "passive+no_connect"))
    )
  )
)
